# BLE_MCU.net
KiCad netlist of a schematic drawn in Altium Designer
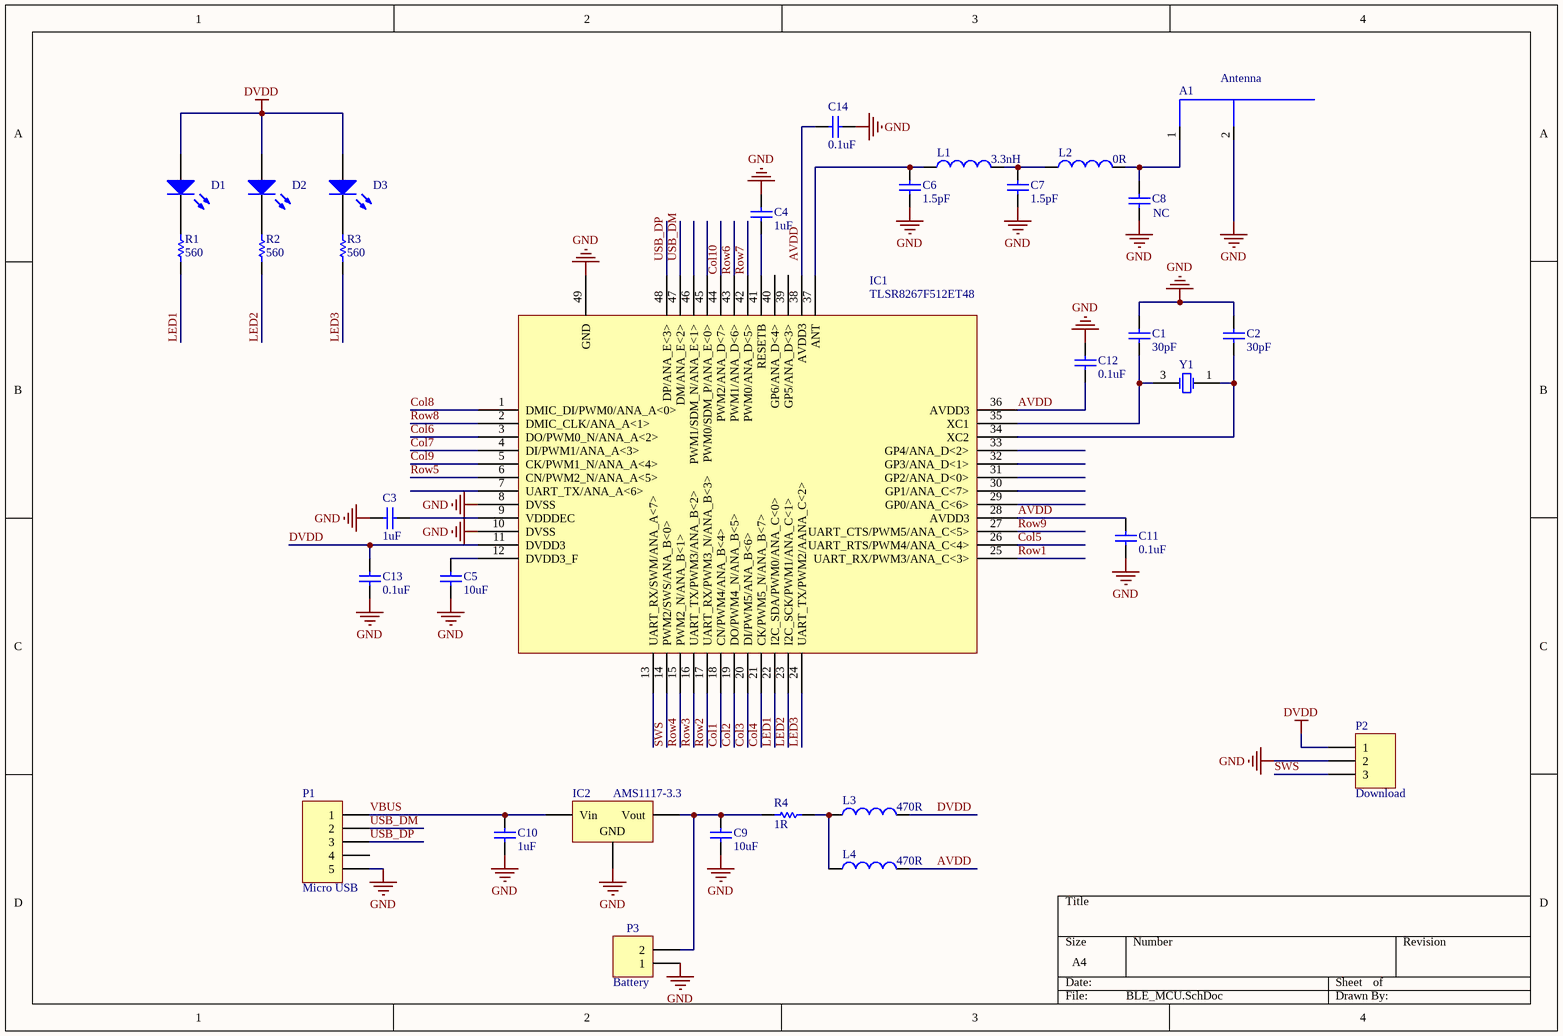
[diagram p0: BLE_MCU.SchDoc]

(export (version "E")
  (design (tool "Eeschema 10.0.6"))
  (components
    (comp (ref "A1")
      (value "Antenna")
      (footprint "ANT_IFA_TI_DN0007")
      (libsource (lib "Telink") (part "Antenna"))
    )
    (comp (ref "C1")
      (value "30pF")
      (footprint "C603_4MOD")
      (description "Capacitor")
      (fields (field (name "Comment") "Cap") (field (name "PUBLISHER") "Altium Limited"))
      (libsource (lib "Miscellaneous Devices") (part "Cap"))
    )
    (comp (ref "C2")
      (value "30pF")
      (footprint "C603_4MOD")
      (description "Capacitor")
      (fields (field (name "Comment") "Cap") (field (name "PUBLISHER") "Altium Limited"))
      (libsource (lib "Miscellaneous Devices") (part "Cap"))
    )
    (comp (ref "C3")
      (value "1uF")
      (footprint "C603_4MOD")
      (description "Capacitor")
      (fields (field (name "Comment") "Cap") (field (name "PUBLISHER") "Altium Limited"))
      (libsource (lib "Miscellaneous Devices") (part "Cap"))
    )
    (comp (ref "C4")
      (value "1uF")
      (footprint "C603_4MOD")
      (description "Capacitor")
      (fields (field (name "Comment") "Cap") (field (name "PUBLISHER") "Altium Limited"))
      (libsource (lib "Miscellaneous Devices") (part "Cap"))
    )
    (comp (ref "C5")
      (value "10uF")
      (footprint "L0805_POWER_4MOD")
      (description "Capacitor")
      (fields (field (name "Comment") "Cap") (field (name "PUBLISHER") "Altium Limited"))
      (libsource (lib "Miscellaneous Devices") (part "Cap"))
    )
    (comp (ref "C6")
      (value "1.5pF")
      (footprint "C402_4MOD")
      (description "Capacitor")
      (fields (field (name "Comment") "Cap") (field (name "PUBLISHER") "Altium Limited"))
      (libsource (lib "Miscellaneous Devices") (part "Cap"))
    )
    (comp (ref "C7")
      (value "1.5pF")
      (footprint "C402_4MOD")
      (description "Capacitor")
      (fields (field (name "Comment") "Cap") (field (name "PUBLISHER") "Altium Limited"))
      (libsource (lib "Miscellaneous Devices") (part "Cap"))
    )
    (comp (ref "C8")
      (value "NC")
      (footprint "C402_4MOD")
      (description "Capacitor")
      (fields (field (name "PUBLISHER") "Altium Limited"))
      (libsource (lib "Miscellaneous Devices") (part "Cap"))
    )
    (comp (ref "C9")
      (value "10uF")
      (footprint "L0805_POWER_4MOD")
      (description "Capacitor")
      (fields (field (name "Comment") "Cap") (field (name "PUBLISHER") "Altium Limited"))
      (libsource (lib "Miscellaneous Devices") (part "Cap"))
    )
    (comp (ref "C10")
      (value "1uF")
      (footprint "C603_4MOD")
      (description "Capacitor")
      (fields (field (name "Comment") "Cap") (field (name "PUBLISHER") "Altium Limited"))
      (libsource (lib "Miscellaneous Devices") (part "Cap"))
    )
    (comp (ref "C11")
      (value "0.1uF")
      (footprint "C603_4MOD")
      (description "Capacitor")
      (fields (field (name "Comment") "Cap") (field (name "PUBLISHER") "Altium Limited"))
      (libsource (lib "Miscellaneous Devices") (part "Cap"))
    )
    (comp (ref "C12")
      (value "0.1uF")
      (footprint "C603_4MOD")
      (description "Capacitor")
      (fields (field (name "Comment") "Cap") (field (name "PUBLISHER") "Altium Limited"))
      (libsource (lib "Miscellaneous Devices") (part "Cap"))
    )
    (comp (ref "C13")
      (value "0.1uF")
      (footprint "C603_4MOD")
      (description "Capacitor")
      (fields (field (name "Comment") "Cap") (field (name "PUBLISHER") "Altium Limited"))
      (libsource (lib "Miscellaneous Devices") (part "Cap"))
    )
    (comp (ref "C14")
      (value "0.1uF")
      (footprint "C603_4MOD")
      (description "Capacitor")
      (fields (field (name "Comment") "Cap") (field (name "PUBLISHER") "Altium Limited"))
      (libsource (lib "Miscellaneous Devices") (part "Cap"))
    )
    (comp (ref "D1")
      (value "LED2")
      (footprint "3.8mm")
      (description "Typical RED, GREEN, YELLOW, AMBER GaAs LED")
      (fields (field (name "PUBLISHER") "Altium Limited"))
      (libsource (lib "Miscellaneous Devices") (part "LED2"))
    )
    (comp (ref "D2")
      (value "LED2")
      (footprint "3.8mm")
      (description "Typical RED, GREEN, YELLOW, AMBER GaAs LED")
      (fields (field (name "PUBLISHER") "Altium Limited"))
      (libsource (lib "Miscellaneous Devices") (part "LED2"))
    )
    (comp (ref "D3")
      (value "LED2")
      (footprint "3.8mm")
      (description "Typical RED, GREEN, YELLOW, AMBER GaAs LED")
      (fields (field (name "PUBLISHER") "Altium Limited"))
      (libsource (lib "Miscellaneous Devices") (part "LED2"))
    )
    (comp (ref "IC1")
      (value "TLSR8267F512ET48")
      (footprint "CC26XX_QFN48(7X7)_0P5")
      (libsource (lib "Telink") (part "TLSR8267F512ET48"))
    )
    (comp (ref "IC2")
      (value "AMS1117-3.3")
      (footprint "SOT-223")
      (description "Voltage Regulator")
      (fields (field (name "PUBLISHER") "Altium Limited"))
      (libsource (lib "Miscellaneous Devices") (part "Volt Reg"))
    )
    (comp (ref "L1")
      (value "3.3nH")
      (footprint "L0402_4MOD")
      (description "Inductor")
      (fields (field (name "PUBLISHER") "Altium Limited"))
      (libsource (lib "Miscellaneous Devices") (part "Inductor"))
    )
    (comp (ref "L2")
      (value "0R")
      (footprint "L0402_4MOD")
      (description "Inductor")
      (fields (field (name "PUBLISHER") "Altium Limited"))
      (libsource (lib "Miscellaneous Devices") (part "Inductor"))
    )
    (comp (ref "L3")
      (value "470R")
      (footprint "L0805_POWER_4MOD")
      (description "Inductor")
      (fields (field (name "PUBLISHER") "Altium Limited"))
      (libsource (lib "Miscellaneous Devices") (part "Inductor"))
    )
    (comp (ref "L4")
      (value "470R")
      (footprint "L0805_POWER_4MOD")
      (description "Inductor")
      (fields (field (name "PUBLISHER") "Altium Limited"))
      (libsource (lib "Miscellaneous Devices") (part "Inductor"))
    )
    (comp (ref "P1")
      (value "Micro USB")
      (footprint "MICROUSB")
      (description "Header, 5-Pin")
      (fields (field (name "PUBLISHER") "Altium Limited"))
      (libsource (lib "Miscellaneous Connectors") (part "MHDR1X5"))
    )
    (comp (ref "P2")
      (value "Download")
      (footprint "SWS")
      (description "Header, 3-Pin")
      (fields (field (name "PUBLISHER") "Altium Limited"))
      (libsource (lib "Miscellaneous Connectors") (part "Header 3"))
    )
    (comp (ref "P3")
      (value "Battery")
      (footprint "HDR1X2")
      (description "Header, 2-Pin")
      (fields (field (name "PUBLISHER") "Altium Limited"))
      (libsource (lib "Miscellaneous Connectors") (part "Header 2"))
    )
    (comp (ref "R1")
      (value "560")
      (footprint "L0805_POWER_4MOD")
      (description "Resistor")
      (fields (field (name "Comment") "Res1") (field (name "PUBLISHER") "Altium Limited"))
      (libsource (lib "Miscellaneous Devices") (part "Res1"))
    )
    (comp (ref "R2")
      (value "560")
      (footprint "L0805_POWER_4MOD")
      (description "Resistor")
      (fields (field (name "Comment") "Res1") (field (name "PUBLISHER") "Altium Limited"))
      (libsource (lib "Miscellaneous Devices") (part "Res1"))
    )
    (comp (ref "R3")
      (value "560")
      (footprint "L0805_POWER_4MOD")
      (description "Resistor")
      (fields (field (name "Comment") "Res1") (field (name "PUBLISHER") "Altium Limited"))
      (libsource (lib "Miscellaneous Devices") (part "Res1"))
    )
    (comp (ref "R4")
      (value "1R")
      (footprint "L0805_POWER_4MOD")
      (description "Resistor")
      (fields (field (name "Comment") "Res1") (field (name "PUBLISHER") "Altium Limited"))
      (libsource (lib "Miscellaneous Devices") (part "Res1"))
    )
    (comp (ref "Y1")
      (value "XTAL")
      (footprint "XTAL_SMD_3225(3.2X2.5)")
      (description "Crystal Oscillator")
      (fields (field (name "PUBLISHER") "Altium Limited"))
      (libsource (lib "Miscellaneous Devices") (part "XTAL"))
    )
  )
  (nets
    (net (code "1") (name "/AVDD") (class "Default")
      (node (ref "C11") (pin "1") (pinfunction "1_1") (pintype "passive"))
      (node (ref "C12") (pin "2") (pinfunction "2_2") (pintype "passive"))
      (node (ref "C14") (pin "1") (pinfunction "1_1") (pintype "passive"))
      (node (ref "IC1") (pin "28") (pinfunction "AVDD3_28") (pintype "passive"))
      (node (ref "IC1") (pin "36") (pinfunction "AVDD3_36") (pintype "passive"))
      (node (ref "IC1") (pin "38") (pinfunction "AVDD3_38") (pintype "passive"))
      (node (ref "L4") (pin "2") (pinfunction "2_2") (pintype "passive"))
    )
    (net (code "2") (name "/Col1") (class "Default")
      (node (ref "IC1") (pin "18") (pinfunction "CN/PWM4/ANA_B<4>_18") (pintype "passive"))
    )
    (net (code "3") (name "/Col2") (class "Default")
      (node (ref "IC1") (pin "19") (pinfunction "DO/PWM4_N/ANA_B<5>_19") (pintype "passive"))
    )
    (net (code "4") (name "/Col3") (class "Default")
      (node (ref "IC1") (pin "20") (pinfunction "DI/PWM5/ANA_B<6>_20") (pintype "passive"))
    )
    (net (code "5") (name "/Col4") (class "Default")
      (node (ref "IC1") (pin "21") (pinfunction "CK/PWM5_N/ANA_B<7>_21") (pintype "passive"))
    )
    (net (code "6") (name "/Col5") (class "Default")
      (node (ref "IC1") (pin "26") (pinfunction "UART_RTS/PWM4/ANA_C<4>_26") (pintype "passive"))
    )
    (net (code "7") (name "/Col6") (class "Default")
      (node (ref "IC1") (pin "3") (pinfunction "DO/PWM0_N/ANA_A<2>_3") (pintype "passive"))
    )
    (net (code "8") (name "/Col7") (class "Default")
      (node (ref "IC1") (pin "4") (pinfunction "DI/PWM1/ANA_A<3>_4") (pintype "passive"))
    )
    (net (code "9") (name "/Col8") (class "Default")
      (node (ref "IC1") (pin "1") (pinfunction "DMIC_DI/PWM0/ANA_A<0>_1") (pintype "passive"))
    )
    (net (code "10") (name "/Col9") (class "Default")
      (node (ref "IC1") (pin "5") (pinfunction "CK/PWM1_N/ANA_A<4>_5") (pintype "passive"))
    )
    (net (code "11") (name "/Col10") (class "Default")
      (node (ref "IC1") (pin "44") (pinfunction "PWM2/ANA_D<7>_44") (pintype "passive"))
    )
    (net (code "12") (name "/LED1") (class "Default")
      (node (ref "IC1") (pin "22") (pinfunction "I2C_SDA/PWM0/ANA_C<0>_22") (pintype "passive"))
      (node (ref "R1") (pin "1") (pinfunction "1_1") (pintype "passive"))
    )
    (net (code "13") (name "/LED2") (class "Default")
      (node (ref "IC1") (pin "23") (pinfunction "I2C_SCK/PWM1/ANA_C<1>_23") (pintype "passive"))
      (node (ref "R2") (pin "1") (pinfunction "1_1") (pintype "passive"))
    )
    (net (code "14") (name "/LED3") (class "Default")
      (node (ref "IC1") (pin "24") (pinfunction "UART_TX/PWM2/AANA_C<2>_24") (pintype "passive"))
      (node (ref "R3") (pin "1") (pinfunction "1_1") (pintype "passive"))
    )
    (net (code "15") (name "/Row1") (class "Default")
      (node (ref "IC1") (pin "25") (pinfunction "UART_RX/PWM3/ANA_C<3>_25") (pintype "passive"))
    )
    (net (code "16") (name "/Row2") (class "Default")
      (node (ref "IC1") (pin "17") (pinfunction "UART_RX/PWM3_N/ANA_B<3>_17") (pintype "passive"))
    )
    (net (code "17") (name "/Row3") (class "Default")
      (node (ref "IC1") (pin "16") (pinfunction "UART_TX/PWM3/ANA_B<2>_16") (pintype "passive"))
    )
    (net (code "18") (name "/Row4") (class "Default")
      (node (ref "IC1") (pin "15") (pinfunction "PWM2_N/ANA_B<1>_15") (pintype "passive"))
    )
    (net (code "19") (name "/Row5") (class "Default")
      (node (ref "IC1") (pin "6") (pinfunction "CN/PWM2_N/ANA_A<5>_6") (pintype "passive"))
    )
    (net (code "20") (name "/Row6") (class "Default")
      (node (ref "IC1") (pin "43") (pinfunction "PWM1/ANA_D<6>_43") (pintype "passive"))
    )
    (net (code "21") (name "/Row7") (class "Default")
      (node (ref "IC1") (pin "42") (pinfunction "PWM0/ANA_D<5>_42") (pintype "passive"))
    )
    (net (code "22") (name "/Row8") (class "Default")
      (node (ref "IC1") (pin "2") (pinfunction "DMIC_CLK/ANA_A<1>_2") (pintype "passive"))
    )
    (net (code "23") (name "/Row9") (class "Default")
      (node (ref "IC1") (pin "27") (pinfunction "UART_CTS/PWM5/ANA_C<5>_27") (pintype "passive"))
    )
    (net (code "24") (name "/SWS") (class "Default")
      (node (ref "IC1") (pin "14") (pinfunction "PWM2/SWS/ANA_B<0>_14") (pintype "passive"))
      (node (ref "P2") (pin "3") (pinfunction "3_3") (pintype "passive"))
    )
    (net (code "25") (name "/USB_DM") (class "Default")
      (node (ref "IC1") (pin "47") (pinfunction "DM/ANA_E<2>_47") (pintype "passive"))
      (node (ref "P1") (pin "2") (pinfunction "2_2") (pintype "passive"))
    )
    (net (code "26") (name "/USB_DP") (class "Default")
      (node (ref "IC1") (pin "48") (pinfunction "DP/ANA_E<3>_48") (pintype "passive"))
      (node (ref "P1") (pin "3") (pinfunction "3_3") (pintype "passive"))
    )
    (net (code "27") (name "/VBUS") (class "Default")
      (node (ref "C10") (pin "1") (pinfunction "1_1") (pintype "passive"))
      (node (ref "IC2") (pin "3") (pinfunction "Vin_3") (pintype "passive"))
      (node (ref "P1") (pin "1") (pinfunction "1_1") (pintype "passive"))
    )
    (net (code "28") (name "DVDD") (class "Default")
      (node (ref "C13") (pin "1") (pinfunction "1_1") (pintype "passive"))
      (node (ref "D1") (pin "1") (pinfunction "A_1") (pintype "passive"))
      (node (ref "D2") (pin "1") (pinfunction "A_1") (pintype "passive"))
      (node (ref "D3") (pin "1") (pinfunction "A_1") (pintype "passive"))
      (node (ref "IC1") (pin "11") (pinfunction "DVDD3_11") (pintype "passive"))
      (node (ref "L3") (pin "2") (pinfunction "2_2") (pintype "passive"))
      (node (ref "P2") (pin "1") (pinfunction "1_1") (pintype "passive"))
    )
    (net (code "29") (name "GND") (class "Default")
      (node (ref "A1") (pin "2") (pinfunction "GND_2") (pintype "passive"))
      (node (ref "C1") (pin "2") (pinfunction "2_2") (pintype "passive"))
      (node (ref "C10") (pin "2") (pinfunction "2_2") (pintype "passive"))
      (node (ref "C11") (pin "2") (pinfunction "2_2") (pintype "passive"))
      (node (ref "C12") (pin "1") (pinfunction "1_1") (pintype "passive"))
      (node (ref "C13") (pin "2") (pinfunction "2_2") (pintype "passive"))
      (node (ref "C14") (pin "2") (pinfunction "2_2") (pintype "passive"))
      (node (ref "C2") (pin "2") (pinfunction "2_2") (pintype "passive"))
      (node (ref "C3") (pin "2") (pinfunction "2_2") (pintype "passive"))
      (node (ref "C4") (pin "1") (pinfunction "1_1") (pintype "passive"))
      (node (ref "C5") (pin "2") (pinfunction "2_2") (pintype "passive"))
      (node (ref "C6") (pin "2") (pinfunction "2_2") (pintype "passive"))
      (node (ref "C7") (pin "2") (pinfunction "2_2") (pintype "passive"))
      (node (ref "C8") (pin "2") (pinfunction "2_2") (pintype "passive"))
      (node (ref "C9") (pin "2") (pinfunction "2_2") (pintype "passive"))
      (node (ref "IC1") (pin "10") (pinfunction "DVSS_10") (pintype "passive"))
      (node (ref "IC1") (pin "49") (pinfunction "GND_49") (pintype "passive"))
      (node (ref "IC1") (pin "8") (pinfunction "DVSS_8") (pintype "passive"))
      (node (ref "IC2") (pin "1") (pinfunction "GND_1") (pintype "passive"))
      (node (ref "P1") (pin "5") (pinfunction "5_5") (pintype "passive"))
      (node (ref "P2") (pin "2") (pinfunction "2_2") (pintype "passive"))
      (node (ref "P3") (pin "1") (pinfunction "1_1") (pintype "passive"))
    )
    (net (code "30") (name "Net-(A1-Antenna)") (class "Default")
      (node (ref "A1") (pin "1") (pinfunction "Antenna_1") (pintype "passive"))
      (node (ref "C8") (pin "1") (pinfunction "1_1") (pintype "passive"))
      (node (ref "L2") (pin "2") (pinfunction "2_2") (pintype "passive"))
    )
    (net (code "31") (name "Net-(C7-Pad1)") (class "Default")
      (node (ref "C7") (pin "1") (pinfunction "1_1") (pintype "passive"))
      (node (ref "L1") (pin "2") (pinfunction "2_2") (pintype "passive"))
      (node (ref "L2") (pin "1") (pinfunction "1_1") (pintype "passive"))
    )
    (net (code "32") (name "Net-(D1-K)") (class "Default")
      (node (ref "D1") (pin "2") (pinfunction "K_2") (pintype "passive"))
      (node (ref "R1") (pin "2") (pinfunction "2_2") (pintype "passive"))
    )
    (net (code "33") (name "Net-(D2-K)") (class "Default")
      (node (ref "D2") (pin "2") (pinfunction "K_2") (pintype "passive"))
      (node (ref "R2") (pin "2") (pinfunction "2_2") (pintype "passive"))
    )
    (net (code "34") (name "Net-(D3-K)") (class "Default")
      (node (ref "D3") (pin "2") (pinfunction "K_2") (pintype "passive"))
      (node (ref "R3") (pin "2") (pinfunction "2_2") (pintype "passive"))
    )
    (net (code "35") (name "Net-(IC1-ANT)") (class "Default")
      (node (ref "C6") (pin "1") (pinfunction "1_1") (pintype "passive"))
      (node (ref "IC1") (pin "37") (pinfunction "ANT_37") (pintype "passive"))
      (node (ref "L1") (pin "1") (pinfunction "1_1") (pintype "passive"))
    )
    (net (code "36") (name "Net-(IC1-DVDD3_F)") (class "Default")
      (node (ref "C5") (pin "1") (pinfunction "1_1") (pintype "passive"))
      (node (ref "IC1") (pin "12") (pinfunction "DVDD3_F_12") (pintype "passive"))
    )
    (net (code "37") (name "Net-(IC1-RESETB)") (class "Default")
      (node (ref "C4") (pin "2") (pinfunction "2_2") (pintype "passive"))
      (node (ref "IC1") (pin "41") (pinfunction "RESETB_41") (pintype "passive"))
    )
    (net (code "38") (name "Net-(IC1-VDDDEC)") (class "Default")
      (node (ref "C3") (pin "1") (pinfunction "1_1") (pintype "passive"))
      (node (ref "IC1") (pin "9") (pinfunction "VDDDEC_9") (pintype "passive"))
    )
    (net (code "39") (name "Net-(IC1-XC1)") (class "Default")
      (node (ref "C1") (pin "1") (pinfunction "1_1") (pintype "passive"))
      (node (ref "IC1") (pin "35") (pinfunction "XC1_35") (pintype "passive"))
      (node (ref "Y1") (pin "3") (pinfunction "OSC2_3") (pintype "passive"))
    )
    (net (code "40") (name "Net-(IC1-XC2)") (class "Default")
      (node (ref "C2") (pin "1") (pinfunction "1_1") (pintype "passive"))
      (node (ref "IC1") (pin "34") (pinfunction "XC2_34") (pintype "passive"))
      (node (ref "Y1") (pin "1") (pinfunction "OSC1_1") (pintype "passive"))
    )
    (net (code "41") (name "Net-(IC2-Vout)") (class "Default")
      (node (ref "C9") (pin "1") (pinfunction "1_1") (pintype "passive"))
      (node (ref "IC2") (pin "2") (pinfunction "Vout_2") (pintype "passive"))
      (node (ref "P3") (pin "2") (pinfunction "2_2") (pintype "passive"))
      (node (ref "R4") (pin "2") (pinfunction "2_2") (pintype "passive"))
    )
    (net (code "42") (name "Net-(L3-Pad1)") (class "Default")
      (node (ref "L3") (pin "1") (pinfunction "1_1") (pintype "passive"))
      (node (ref "L4") (pin "1") (pinfunction "1_1") (pintype "passive"))
      (node (ref "R4") (pin "1") (pinfunction "1_1") (pintype "passive"))
    )
    (net (code "43") (name "unconnected-(IC1-GP0{slash}ANA_C<6>-Pad29)") (class "Default")
      (node (ref "IC1") (pin "29") (pinfunction "GP0/ANA_C<6>_29") (pintype "passive"))
    )
    (net (code "44") (name "unconnected-(IC1-GP1{slash}ANA_C<7>-Pad30)") (class "Default")
      (node (ref "IC1") (pin "30") (pinfunction "GP1/ANA_C<7>_30") (pintype "passive"))
    )
    (net (code "45") (name "unconnected-(IC1-GP2{slash}ANA_D<0>-Pad31)") (class "Default")
      (node (ref "IC1") (pin "31") (pinfunction "GP2/ANA_D<0>_31") (pintype "passive"))
    )
    (net (code "46") (name "unconnected-(IC1-GP3{slash}ANA_D<1>-Pad32)") (class "Default")
      (node (ref "IC1") (pin "32") (pinfunction "GP3/ANA_D<1>_32") (pintype "passive"))
    )
    (net (code "47") (name "unconnected-(IC1-GP4{slash}ANA_D<2>-Pad33)") (class "Default")
      (node (ref "IC1") (pin "33") (pinfunction "GP4/ANA_D<2>_33") (pintype "passive"))
    )
    (net (code "48") (name "unconnected-(IC1-GP5{slash}ANA_D<3>-Pad39)") (class "Default")
      (node (ref "IC1") (pin "39") (pinfunction "GP5/ANA_D<3>_39") (pintype "passive"))
    )
    (net (code "49") (name "unconnected-(IC1-GP6{slash}ANA_D<4>-Pad40)") (class "Default")
      (node (ref "IC1") (pin "40") (pinfunction "GP6/ANA_D<4>_40") (pintype "passive"))
    )
    (net (code "50") (name "unconnected-(IC1-PWM0{slash}SDM_P{slash}ANA_E<0>-Pad45)") (class "Default")
      (node (ref "IC1") (pin "45") (pinfunction "PWM0/SDM_P/ANA_E<0>_45") (pintype "passive"))
    )
    (net (code "51") (name "unconnected-(IC1-PWM1{slash}SDM_N{slash}ANA_E<1>-Pad46)") (class "Default")
      (node (ref "IC1") (pin "46") (pinfunction "PWM1/SDM_N/ANA_E<1>_46") (pintype "passive"))
    )
    (net (code "52") (name "unconnected-(IC1-UART_RX{slash}SWM{slash}ANA_A<7>-Pad13)") (class "Default")
      (node (ref "IC1") (pin "13") (pinfunction "UART_RX/SWM/ANA_A<7>_13") (pintype "passive"))
    )
    (net (code "53") (name "unconnected-(IC1-UART_TX{slash}ANA_A<6>-Pad7)") (class "Default")
      (node (ref "IC1") (pin "7") (pinfunction "UART_TX/ANA_A<6>_7") (pintype "passive"))
    )
    (net (code "54") (name "unconnected-(P1-Pad4)") (class "Default")
      (node (ref "P1") (pin "4") (pinfunction "4_4") (pintype "passive"))
    )
  )
)
